# SheetTest.net
KiCad netlist of a schematic drawn in Altium Designer
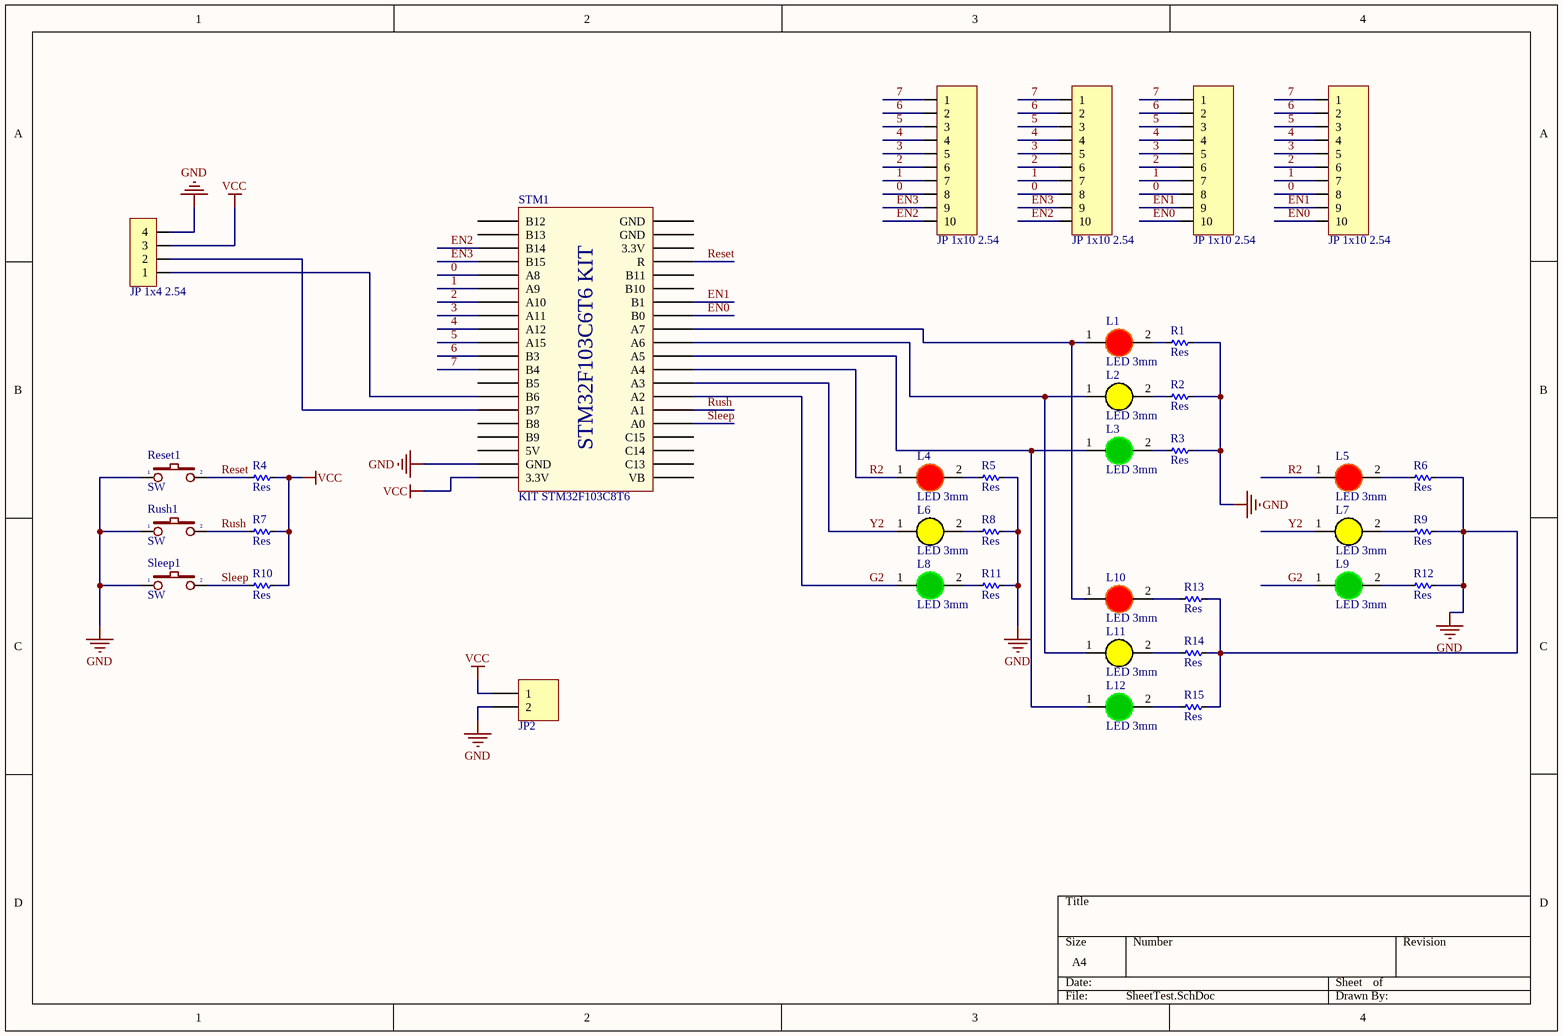
[diagram p0: SheetTest.SchDoc]

(export (version "E")
  (design (tool "Eeschema 10.0.6"))
  (components
    (comp (ref "JP1")
      (value "JP 1x4 2.54")
      (footprint "JP 1x4 DT")
      (description "Cắm")
      (libsource (lib "Altium_Lib_by_KhueNguyenCreator") (part "JP 1x4 2.54 Duc Thang"))
    )
    (comp (ref "JP2")
      (value "Header 2_1")
      (footprint "HED2")
      (description "Header, 2-Pin")
      (fields (field (name "MANUFACTURER") "Generic Components"))
      (libsource (lib "syhaunguyen") (part "Header 2_1"))
    )
    (comp (ref "L1")
      (value "LED 3mm")
      (footprint "LED-3MM-RED")
      (description "Cắm")
      (libsource (lib "Altium_Lib_by_KhueNguyenCreator") (part "LED 3mm Do"))
    )
    (comp (ref "L2")
      (value "LED 3mm")
      (footprint "LED-3MM-YELLOW")
      (description "Cắm")
      (libsource (lib "Altium_Lib_by_KhueNguyenCreator") (part "LED 3mm Vang"))
    )
    (comp (ref "L3")
      (value "LED 3mm")
      (footprint "LED-3MM-GREEN")
      (description "Cắm")
      (libsource (lib "Altium_Lib_by_KhueNguyenCreator") (part "LED 3mm Xanh La"))
    )
    (comp (ref "L4")
      (value "LED 3mm")
      (footprint "LED-3MM-RED")
      (description "Cắm")
      (libsource (lib "Altium_Lib_by_KhueNguyenCreator") (part "LED 3mm Do"))
    )
    (comp (ref "L5")
      (value "LED 3mm")
      (footprint "LED-3MM-RED")
      (description "Cắm")
      (libsource (lib "Altium_Lib_by_KhueNguyenCreator") (part "LED 3mm Do"))
    )
    (comp (ref "L6")
      (value "LED 3mm")
      (footprint "LED-3MM-YELLOW")
      (description "Cắm")
      (libsource (lib "Altium_Lib_by_KhueNguyenCreator") (part "LED 3mm Vang"))
    )
    (comp (ref "L7")
      (value "LED 3mm")
      (footprint "LED-3MM-YELLOW")
      (description "Cắm")
      (libsource (lib "Altium_Lib_by_KhueNguyenCreator") (part "LED 3mm Vang"))
    )
    (comp (ref "L8")
      (value "LED 3mm")
      (footprint "LED-3MM-GREEN")
      (description "Cắm")
      (libsource (lib "Altium_Lib_by_KhueNguyenCreator") (part "LED 3mm Xanh La"))
    )
    (comp (ref "L9")
      (value "LED 3mm")
      (footprint "LED-3MM-GREEN")
      (description "Cắm")
      (libsource (lib "Altium_Lib_by_KhueNguyenCreator") (part "LED 3mm Xanh La"))
    )
    (comp (ref "L10")
      (value "LED 3mm")
      (footprint "LED-3MM-RED")
      (description "Cắm")
      (libsource (lib "Altium_Lib_by_KhueNguyenCreator") (part "LED 3mm Do"))
    )
    (comp (ref "L11")
      (value "LED 3mm")
      (footprint "LED-3MM-YELLOW")
      (description "Cắm")
      (libsource (lib "Altium_Lib_by_KhueNguyenCreator") (part "LED 3mm Vang"))
    )
    (comp (ref "L12")
      (value "LED 3mm")
      (footprint "LED-3MM-GREEN")
      (description "Cắm")
      (libsource (lib "Altium_Lib_by_KhueNguyenCreator") (part "LED 3mm Xanh La"))
    )
    (comp (ref "Led1")
      (value "JP 1x10 2.54")
      (footprint "JP 1x10 DT")
      (description "Cắm")
      (libsource (lib "Altium_Lib_by_KhueNguyenCreator") (part "JP 1x10 2.54 Duc Thang"))
    )
    (comp (ref "Led2")
      (value "JP 1x10 2.54")
      (footprint "JP 1x10 DT")
      (description "Cắm")
      (libsource (lib "Altium_Lib_by_KhueNguyenCreator") (part "JP 1x10 2.54 Duc Thang"))
    )
    (comp (ref "Led3")
      (value "JP 1x10 2.54")
      (footprint "JP 1x10 DT")
      (description "Cắm")
      (libsource (lib "Altium_Lib_by_KhueNguyenCreator") (part "JP 1x10 2.54 Duc Thang"))
    )
    (comp (ref "Led4")
      (value "JP 1x10 2.54")
      (footprint "JP 1x10 DT")
      (description "Cắm")
      (libsource (lib "Altium_Lib_by_KhueNguyenCreator") (part "JP 1x10 2.54 Duc Thang"))
    )
    (comp (ref "R1")
      (value "Res")
      (footprint "RES-1/2W")
      (fields
        (field (name "MANUFACTURER") "Generic Components")
        (field (name "PUBLISHER") "Altium Hobart Technology Centre")
      )
      (libsource (lib "thu vien 3d") (part "Res"))
    )
    (comp (ref "R2")
      (value "Res")
      (footprint "RES-1/2W")
      (fields
        (field (name "MANUFACTURER") "Generic Components")
        (field (name "PUBLISHER") "Altium Hobart Technology Centre")
      )
      (libsource (lib "thu vien 3d") (part "Res"))
    )
    (comp (ref "R3")
      (value "Res")
      (footprint "RES-1/2W")
      (fields
        (field (name "MANUFACTURER") "Generic Components")
        (field (name "PUBLISHER") "Altium Hobart Technology Centre")
      )
      (libsource (lib "thu vien 3d") (part "Res"))
    )
    (comp (ref "R4")
      (value "Res")
      (footprint "RES-1/2W")
      (fields
        (field (name "MANUFACTURER") "Generic Components")
        (field (name "PUBLISHER") "Altium Hobart Technology Centre")
      )
      (libsource (lib "thu vien 3d") (part "Res"))
    )
    (comp (ref "R5")
      (value "Res")
      (footprint "RES-1/2W")
      (fields
        (field (name "MANUFACTURER") "Generic Components")
        (field (name "PUBLISHER") "Altium Hobart Technology Centre")
      )
      (libsource (lib "thu vien 3d") (part "Res"))
    )
    (comp (ref "R6")
      (value "Res")
      (footprint "RES-1/2W")
      (fields
        (field (name "MANUFACTURER") "Generic Components")
        (field (name "PUBLISHER") "Altium Hobart Technology Centre")
      )
      (libsource (lib "thu vien 3d") (part "Res"))
    )
    (comp (ref "R7")
      (value "Res")
      (footprint "RES-1/2W")
      (fields
        (field (name "MANUFACTURER") "Generic Components")
        (field (name "PUBLISHER") "Altium Hobart Technology Centre")
      )
      (libsource (lib "thu vien 3d") (part "Res"))
    )
    (comp (ref "R8")
      (value "Res")
      (footprint "RES-1/2W")
      (fields
        (field (name "MANUFACTURER") "Generic Components")
        (field (name "PUBLISHER") "Altium Hobart Technology Centre")
      )
      (libsource (lib "thu vien 3d") (part "Res"))
    )
    (comp (ref "R9")
      (value "Res")
      (footprint "RES-1/2W")
      (fields
        (field (name "MANUFACTURER") "Generic Components")
        (field (name "PUBLISHER") "Altium Hobart Technology Centre")
      )
      (libsource (lib "thu vien 3d") (part "Res"))
    )
    (comp (ref "R10")
      (value "Res")
      (footprint "RES-1/2W")
      (fields
        (field (name "MANUFACTURER") "Generic Components")
        (field (name "PUBLISHER") "Altium Hobart Technology Centre")
      )
      (libsource (lib "thu vien 3d") (part "Res"))
    )
    (comp (ref "R11")
      (value "Res")
      (footprint "RES-1/2W")
      (fields
        (field (name "MANUFACTURER") "Generic Components")
        (field (name "PUBLISHER") "Altium Hobart Technology Centre")
      )
      (libsource (lib "thu vien 3d") (part "Res"))
    )
    (comp (ref "R12")
      (value "Res")
      (footprint "RES-1/2W")
      (fields
        (field (name "MANUFACTURER") "Generic Components")
        (field (name "PUBLISHER") "Altium Hobart Technology Centre")
      )
      (libsource (lib "thu vien 3d") (part "Res"))
    )
    (comp (ref "R13")
      (value "Res")
      (footprint "RES-1/2W")
      (fields
        (field (name "MANUFACTURER") "Generic Components")
        (field (name "PUBLISHER") "Altium Hobart Technology Centre")
      )
      (libsource (lib "thu vien 3d") (part "Res"))
    )
    (comp (ref "R14")
      (value "Res")
      (footprint "RES-1/2W")
      (fields
        (field (name "MANUFACTURER") "Generic Components")
        (field (name "PUBLISHER") "Altium Hobart Technology Centre")
      )
      (libsource (lib "thu vien 3d") (part "Res"))
    )
    (comp (ref "R15")
      (value "Res")
      (footprint "RES-1/2W")
      (fields
        (field (name "MANUFACTURER") "Generic Components")
        (field (name "PUBLISHER") "Altium Hobart Technology Centre")
      )
      (libsource (lib "thu vien 3d") (part "Res"))
    )
    (comp (ref "Reset1")
      (value "SW")
      (footprint "SW2")
      (description "Switch button 2 pin")
      (libsource (lib "syhaunguyen") (part "SW2"))
    )
    (comp (ref "Rush1")
      (value "SW")
      (footprint "SW2")
      (description "Switch button 2 pin")
      (libsource (lib "syhaunguyen") (part "SW2"))
    )
    (comp (ref "Sleep1")
      (value "SW")
      (footprint "SW2")
      (description "Switch button 2 pin")
      (libsource (lib "syhaunguyen") (part "SW2"))
    )
    (comp (ref "STM1")
      (value "KIT STM32F103C8T6")
      (footprint "STM32F103 KIT")
      (description "KIT STM32F103C8T6 Bluepill")
      (libsource (lib "Altium_Lib_by_KhueNguyenCreator") (part "STM32f103 Bluepill"))
    )
  )
  (nets
    (net (code "1") (name "/0") (class "Default")
      (node (ref "Led1") (pin "8") (pinfunction "8_8") (pintype "passive"))
      (node (ref "Led2") (pin "8") (pinfunction "8_8") (pintype "passive"))
      (node (ref "Led3") (pin "8") (pinfunction "8_8") (pintype "passive"))
      (node (ref "Led4") (pin "8") (pinfunction "8_8") (pintype "passive"))
      (node (ref "STM1") (pin "5") (pinfunction "A8_5") (pintype "passive"))
    )
    (net (code "2") (name "/1") (class "Default")
      (node (ref "Led1") (pin "7") (pinfunction "7_7") (pintype "passive"))
      (node (ref "Led2") (pin "7") (pinfunction "7_7") (pintype "passive"))
      (node (ref "Led3") (pin "7") (pinfunction "7_7") (pintype "passive"))
      (node (ref "Led4") (pin "7") (pinfunction "7_7") (pintype "passive"))
      (node (ref "STM1") (pin "6") (pinfunction "A9_6") (pintype "passive"))
    )
    (net (code "3") (name "/2") (class "Default")
      (node (ref "Led1") (pin "6") (pinfunction "6_6") (pintype "passive"))
      (node (ref "Led2") (pin "6") (pinfunction "6_6") (pintype "passive"))
      (node (ref "Led3") (pin "6") (pinfunction "6_6") (pintype "passive"))
      (node (ref "Led4") (pin "6") (pinfunction "6_6") (pintype "passive"))
      (node (ref "STM1") (pin "7") (pinfunction "A10_7") (pintype "passive"))
    )
    (net (code "4") (name "/3") (class "Default")
      (node (ref "Led1") (pin "5") (pinfunction "5_5") (pintype "passive"))
      (node (ref "Led2") (pin "5") (pinfunction "5_5") (pintype "passive"))
      (node (ref "Led3") (pin "5") (pinfunction "5_5") (pintype "passive"))
      (node (ref "Led4") (pin "5") (pinfunction "5_5") (pintype "passive"))
      (node (ref "STM1") (pin "8") (pinfunction "A11_8") (pintype "passive"))
    )
    (net (code "5") (name "/4") (class "Default")
      (node (ref "Led1") (pin "4") (pinfunction "4_4") (pintype "passive"))
      (node (ref "Led2") (pin "4") (pinfunction "4_4") (pintype "passive"))
      (node (ref "Led3") (pin "4") (pinfunction "4_4") (pintype "passive"))
      (node (ref "Led4") (pin "4") (pinfunction "4_4") (pintype "passive"))
      (node (ref "STM1") (pin "9") (pinfunction "A12_9") (pintype "passive"))
    )
    (net (code "6") (name "/5") (class "Default")
      (node (ref "Led1") (pin "3") (pinfunction "3_3") (pintype "passive"))
      (node (ref "Led2") (pin "3") (pinfunction "3_3") (pintype "passive"))
      (node (ref "Led3") (pin "3") (pinfunction "3_3") (pintype "passive"))
      (node (ref "Led4") (pin "3") (pinfunction "3_3") (pintype "passive"))
      (node (ref "STM1") (pin "10") (pinfunction "A15_10") (pintype "passive"))
    )
    (net (code "7") (name "/6") (class "Default")
      (node (ref "Led1") (pin "2") (pinfunction "2_2") (pintype "passive"))
      (node (ref "Led2") (pin "2") (pinfunction "2_2") (pintype "passive"))
      (node (ref "Led3") (pin "2") (pinfunction "2_2") (pintype "passive"))
      (node (ref "Led4") (pin "2") (pinfunction "2_2") (pintype "passive"))
      (node (ref "STM1") (pin "11") (pinfunction "B3_11") (pintype "passive"))
    )
    (net (code "8") (name "/7") (class "Default")
      (node (ref "Led1") (pin "1") (pinfunction "1_1") (pintype "passive"))
      (node (ref "Led2") (pin "1") (pinfunction "1_1") (pintype "passive"))
      (node (ref "Led3") (pin "1") (pinfunction "1_1") (pintype "passive"))
      (node (ref "Led4") (pin "1") (pinfunction "1_1") (pintype "passive"))
      (node (ref "STM1") (pin "12") (pinfunction "B4_12") (pintype "passive"))
    )
    (net (code "9") (name "/EN0") (class "Default")
      (node (ref "Led3") (pin "10") (pinfunction "10_10") (pintype "passive"))
      (node (ref "Led4") (pin "10") (pinfunction "10_10") (pintype "passive"))
      (node (ref "STM1") (pin "33") (pinfunction "B0_33") (pintype "passive"))
    )
    (net (code "10") (name "/EN1") (class "Default")
      (node (ref "Led3") (pin "9") (pinfunction "9_9") (pintype "passive"))
      (node (ref "Led4") (pin "9") (pinfunction "9_9") (pintype "passive"))
      (node (ref "STM1") (pin "34") (pinfunction "B1_34") (pintype "passive"))
    )
    (net (code "11") (name "/EN2") (class "Default")
      (node (ref "Led1") (pin "10") (pinfunction "10_10") (pintype "passive"))
      (node (ref "Led2") (pin "10") (pinfunction "10_10") (pintype "passive"))
      (node (ref "STM1") (pin "3") (pinfunction "B14_3") (pintype "passive"))
    )
    (net (code "12") (name "/EN3") (class "Default")
      (node (ref "Led1") (pin "9") (pinfunction "9_9") (pintype "passive"))
      (node (ref "Led2") (pin "9") (pinfunction "9_9") (pintype "passive"))
      (node (ref "STM1") (pin "4") (pinfunction "B15_4") (pintype "passive"))
    )
    (net (code "13") (name "/G2") (class "Default")
      (node (ref "L8") (pin "1") (pinfunction "A_1") (pintype "passive"))
      (node (ref "L9") (pin "1") (pinfunction "A_1") (pintype "passive"))
      (node (ref "STM1") (pin "27") (pinfunction "A2_27") (pintype "passive"))
    )
    (net (code "14") (name "/R2") (class "Default")
      (node (ref "L4") (pin "1") (pinfunction "A_1") (pintype "passive"))
      (node (ref "L5") (pin "1") (pinfunction "A_1") (pintype "passive"))
      (node (ref "STM1") (pin "29") (pinfunction "A4_29") (pintype "passive"))
    )
    (net (code "15") (name "/Reset") (class "Default")
      (node (ref "R4") (pin "2") (pinfunction "2_2") (pintype "passive"))
      (node (ref "Reset1") (pin "2") (pinfunction "2_2") (pintype "passive"))
      (node (ref "STM1") (pin "37") (pinfunction "R_37") (pintype "passive"))
    )
    (net (code "16") (name "/Rush") (class "Default")
      (node (ref "R7") (pin "2") (pinfunction "2_2") (pintype "passive"))
      (node (ref "Rush1") (pin "2") (pinfunction "2_2") (pintype "passive"))
      (node (ref "STM1") (pin "26") (pinfunction "A1_26") (pintype "passive"))
    )
    (net (code "17") (name "/Sleep") (class "Default")
      (node (ref "R10") (pin "2") (pinfunction "2_2") (pintype "passive"))
      (node (ref "STM1") (pin "25") (pinfunction "A0_25") (pintype "passive"))
      (node (ref "Sleep1") (pin "2") (pinfunction "2_2") (pintype "passive"))
    )
    (net (code "18") (name "/Y2") (class "Default")
      (node (ref "L6") (pin "1") (pinfunction "A_1") (pintype "passive"))
      (node (ref "L7") (pin "1") (pinfunction "A_1") (pintype "passive"))
      (node (ref "STM1") (pin "28") (pinfunction "A3_28") (pintype "passive"))
    )
    (net (code "19") (name "GND") (class "Default")
      (node (ref "JP1") (pin "4") (pinfunction "4_4") (pintype "passive"))
      (node (ref "JP2") (pin "2") (pinfunction "2_2") (pintype "passive"))
      (node (ref "R1") (pin "1") (pinfunction "1_1") (pintype "passive"))
      (node (ref "R11") (pin "1") (pinfunction "1_1") (pintype "passive"))
      (node (ref "R12") (pin "1") (pinfunction "1_1") (pintype "passive"))
      (node (ref "R13") (pin "1") (pinfunction "1_1") (pintype "passive"))
      (node (ref "R14") (pin "1") (pinfunction "1_1") (pintype "passive"))
      (node (ref "R15") (pin "1") (pinfunction "1_1") (pintype "passive"))
      (node (ref "R2") (pin "1") (pinfunction "1_1") (pintype "passive"))
      (node (ref "R3") (pin "1") (pinfunction "1_1") (pintype "passive"))
      (node (ref "R5") (pin "1") (pinfunction "1_1") (pintype "passive"))
      (node (ref "R6") (pin "1") (pinfunction "1_1") (pintype "passive"))
      (node (ref "R8") (pin "1") (pinfunction "1_1") (pintype "passive"))
      (node (ref "R9") (pin "1") (pinfunction "1_1") (pintype "passive"))
      (node (ref "Reset1") (pin "1") (pinfunction "1_1") (pintype "passive"))
      (node (ref "Rush1") (pin "1") (pinfunction "1_1") (pintype "passive"))
      (node (ref "STM1") (pin "19") (pinfunction "GND_19") (pintype "passive"))
      (node (ref "Sleep1") (pin "1") (pinfunction "1_1") (pintype "passive"))
    )
    (net (code "20") (name "Net-(L1-A)") (class "Default")
      (node (ref "L1") (pin "1") (pinfunction "A_1") (pintype "passive"))
      (node (ref "L10") (pin "1") (pinfunction "A_1") (pintype "passive"))
      (node (ref "STM1") (pin "32") (pinfunction "A7_32") (pintype "passive"))
    )
    (net (code "21") (name "Net-(L1-K)") (class "Default")
      (node (ref "L1") (pin "2") (pinfunction "K_2") (pintype "passive"))
      (node (ref "R1") (pin "2") (pinfunction "2_2") (pintype "passive"))
    )
    (net (code "22") (name "Net-(L2-K)") (class "Default")
      (node (ref "L2") (pin "2") (pinfunction "K_2") (pintype "passive"))
      (node (ref "R2") (pin "2") (pinfunction "2_2") (pintype "passive"))
    )
    (net (code "23") (name "Net-(L3-K)") (class "Default")
      (node (ref "L3") (pin "2") (pinfunction "K_2") (pintype "passive"))
      (node (ref "R3") (pin "2") (pinfunction "2_2") (pintype "passive"))
    )
    (net (code "24") (name "Net-(L4-K)") (class "Default")
      (node (ref "L4") (pin "2") (pinfunction "K_2") (pintype "passive"))
      (node (ref "R5") (pin "2") (pinfunction "2_2") (pintype "passive"))
    )
    (net (code "25") (name "Net-(L5-K)") (class "Default")
      (node (ref "L5") (pin "2") (pinfunction "K_2") (pintype "passive"))
      (node (ref "R6") (pin "2") (pinfunction "2_2") (pintype "passive"))
    )
    (net (code "26") (name "Net-(L6-K)") (class "Default")
      (node (ref "L6") (pin "2") (pinfunction "K_2") (pintype "passive"))
      (node (ref "R8") (pin "2") (pinfunction "2_2") (pintype "passive"))
    )
    (net (code "27") (name "Net-(L7-K)") (class "Default")
      (node (ref "L7") (pin "2") (pinfunction "K_2") (pintype "passive"))
      (node (ref "R9") (pin "2") (pinfunction "2_2") (pintype "passive"))
    )
    (net (code "28") (name "Net-(L8-K)") (class "Default")
      (node (ref "L8") (pin "2") (pinfunction "K_2") (pintype "passive"))
      (node (ref "R11") (pin "2") (pinfunction "2_2") (pintype "passive"))
    )
    (net (code "29") (name "Net-(L9-K)") (class "Default")
      (node (ref "L9") (pin "2") (pinfunction "K_2") (pintype "passive"))
      (node (ref "R12") (pin "2") (pinfunction "2_2") (pintype "passive"))
    )
    (net (code "30") (name "Net-(L10-K)") (class "Default")
      (node (ref "L10") (pin "2") (pinfunction "K_2") (pintype "passive"))
      (node (ref "R13") (pin "2") (pinfunction "2_2") (pintype "passive"))
    )
    (net (code "31") (name "Net-(L11-A)") (class "Default")
      (node (ref "L11") (pin "1") (pinfunction "A_1") (pintype "passive"))
      (node (ref "L2") (pin "1") (pinfunction "A_1") (pintype "passive"))
      (node (ref "STM1") (pin "31") (pinfunction "A6_31") (pintype "passive"))
    )
    (net (code "32") (name "Net-(L11-K)") (class "Default")
      (node (ref "L11") (pin "2") (pinfunction "K_2") (pintype "passive"))
      (node (ref "R14") (pin "2") (pinfunction "2_2") (pintype "passive"))
    )
    (net (code "33") (name "Net-(L12-A)") (class "Default")
      (node (ref "L12") (pin "1") (pinfunction "A_1") (pintype "passive"))
      (node (ref "L3") (pin "1") (pinfunction "A_1") (pintype "passive"))
      (node (ref "STM1") (pin "30") (pinfunction "A5_30") (pintype "passive"))
    )
    (net (code "34") (name "Net-(L12-K)") (class "Default")
      (node (ref "L12") (pin "2") (pinfunction "K_2") (pintype "passive"))
      (node (ref "R15") (pin "2") (pinfunction "2_2") (pintype "passive"))
    )
    (net (code "35") (name "Net-(STM1-B6)") (class "Default")
      (node (ref "JP1") (pin "1") (pinfunction "1_1") (pintype "passive"))
      (node (ref "STM1") (pin "14") (pinfunction "B6_14") (pintype "passive"))
    )
    (net (code "36") (name "Net-(STM1-B7)") (class "Default")
      (node (ref "JP1") (pin "2") (pinfunction "2_2") (pintype "passive"))
      (node (ref "STM1") (pin "15") (pinfunction "B7_15") (pintype "passive"))
    )
    (net (code "37") (name "VCC") (class "Default")
      (node (ref "JP1") (pin "3") (pinfunction "3_3") (pintype "passive"))
      (node (ref "JP2") (pin "1") (pinfunction "1_1") (pintype "passive"))
      (node (ref "R10") (pin "1") (pinfunction "1_1") (pintype "passive"))
      (node (ref "R4") (pin "1") (pinfunction "1_1") (pintype "passive"))
      (node (ref "R7") (pin "1") (pinfunction "1_1") (pintype "passive"))
      (node (ref "STM1") (pin "20") (pinfunction "3.3V_20") (pintype "passive"))
    )
    (net (code "38") (name "unconnected-(STM1-3.3V-Pad38)") (class "Default")
      (node (ref "STM1") (pin "38") (pinfunction "3.3V_38") (pintype "passive"))
    )
    (net (code "39") (name "unconnected-(STM1-5V-Pad18)") (class "Default")
      (node (ref "STM1") (pin "18") (pinfunction "5V_18") (pintype "passive"))
    )
    (net (code "40") (name "unconnected-(STM1-B5-Pad13)") (class "Default")
      (node (ref "STM1") (pin "13") (pinfunction "B5_13") (pintype "passive"))
    )
    (net (code "41") (name "unconnected-(STM1-B8-Pad16)") (class "Default")
      (node (ref "STM1") (pin "16") (pinfunction "B8_16") (pintype "passive"))
    )
    (net (code "42") (name "unconnected-(STM1-B9-Pad17)") (class "Default")
      (node (ref "STM1") (pin "17") (pinfunction "B9_17") (pintype "passive"))
    )
    (net (code "43") (name "unconnected-(STM1-B10-Pad35)") (class "Default")
      (node (ref "STM1") (pin "35") (pinfunction "B10_35") (pintype "passive"))
    )
    (net (code "44") (name "unconnected-(STM1-B11-Pad36)") (class "Default")
      (node (ref "STM1") (pin "36") (pinfunction "B11_36") (pintype "passive"))
    )
    (net (code "45") (name "unconnected-(STM1-B12-Pad1)") (class "Default")
      (node (ref "STM1") (pin "1") (pinfunction "B12_1") (pintype "passive"))
    )
    (net (code "46") (name "unconnected-(STM1-B13-Pad2)") (class "Default")
      (node (ref "STM1") (pin "2") (pinfunction "B13_2") (pintype "passive"))
    )
    (net (code "47") (name "unconnected-(STM1-C13-Pad22)") (class "Default")
      (node (ref "STM1") (pin "22") (pinfunction "C13_22") (pintype "passive"))
    )
    (net (code "48") (name "unconnected-(STM1-C14-Pad23)") (class "Default")
      (node (ref "STM1") (pin "23") (pinfunction "C14_23") (pintype "passive"))
    )
    (net (code "49") (name "unconnected-(STM1-C15-Pad24)") (class "Default")
      (node (ref "STM1") (pin "24") (pinfunction "C15_24") (pintype "passive"))
    )
    (net (code "50") (name "unconnected-(STM1-GND-Pad39)") (class "Default")
      (node (ref "STM1") (pin "39") (pinfunction "GND_39") (pintype "passive"))
    )
    (net (code "51") (name "unconnected-(STM1-GND-Pad40)") (class "Default")
      (node (ref "STM1") (pin "40") (pinfunction "GND_40") (pintype "passive"))
    )
    (net (code "52") (name "unconnected-(STM1-VB-Pad21)") (class "Default")
      (node (ref "STM1") (pin "21") (pinfunction "VB_21") (pintype "passive"))
    )
  )
)
